# 16_RK3588_MIPI_Interface.net
KiCad netlist of a schematic drawn in Altium Designer
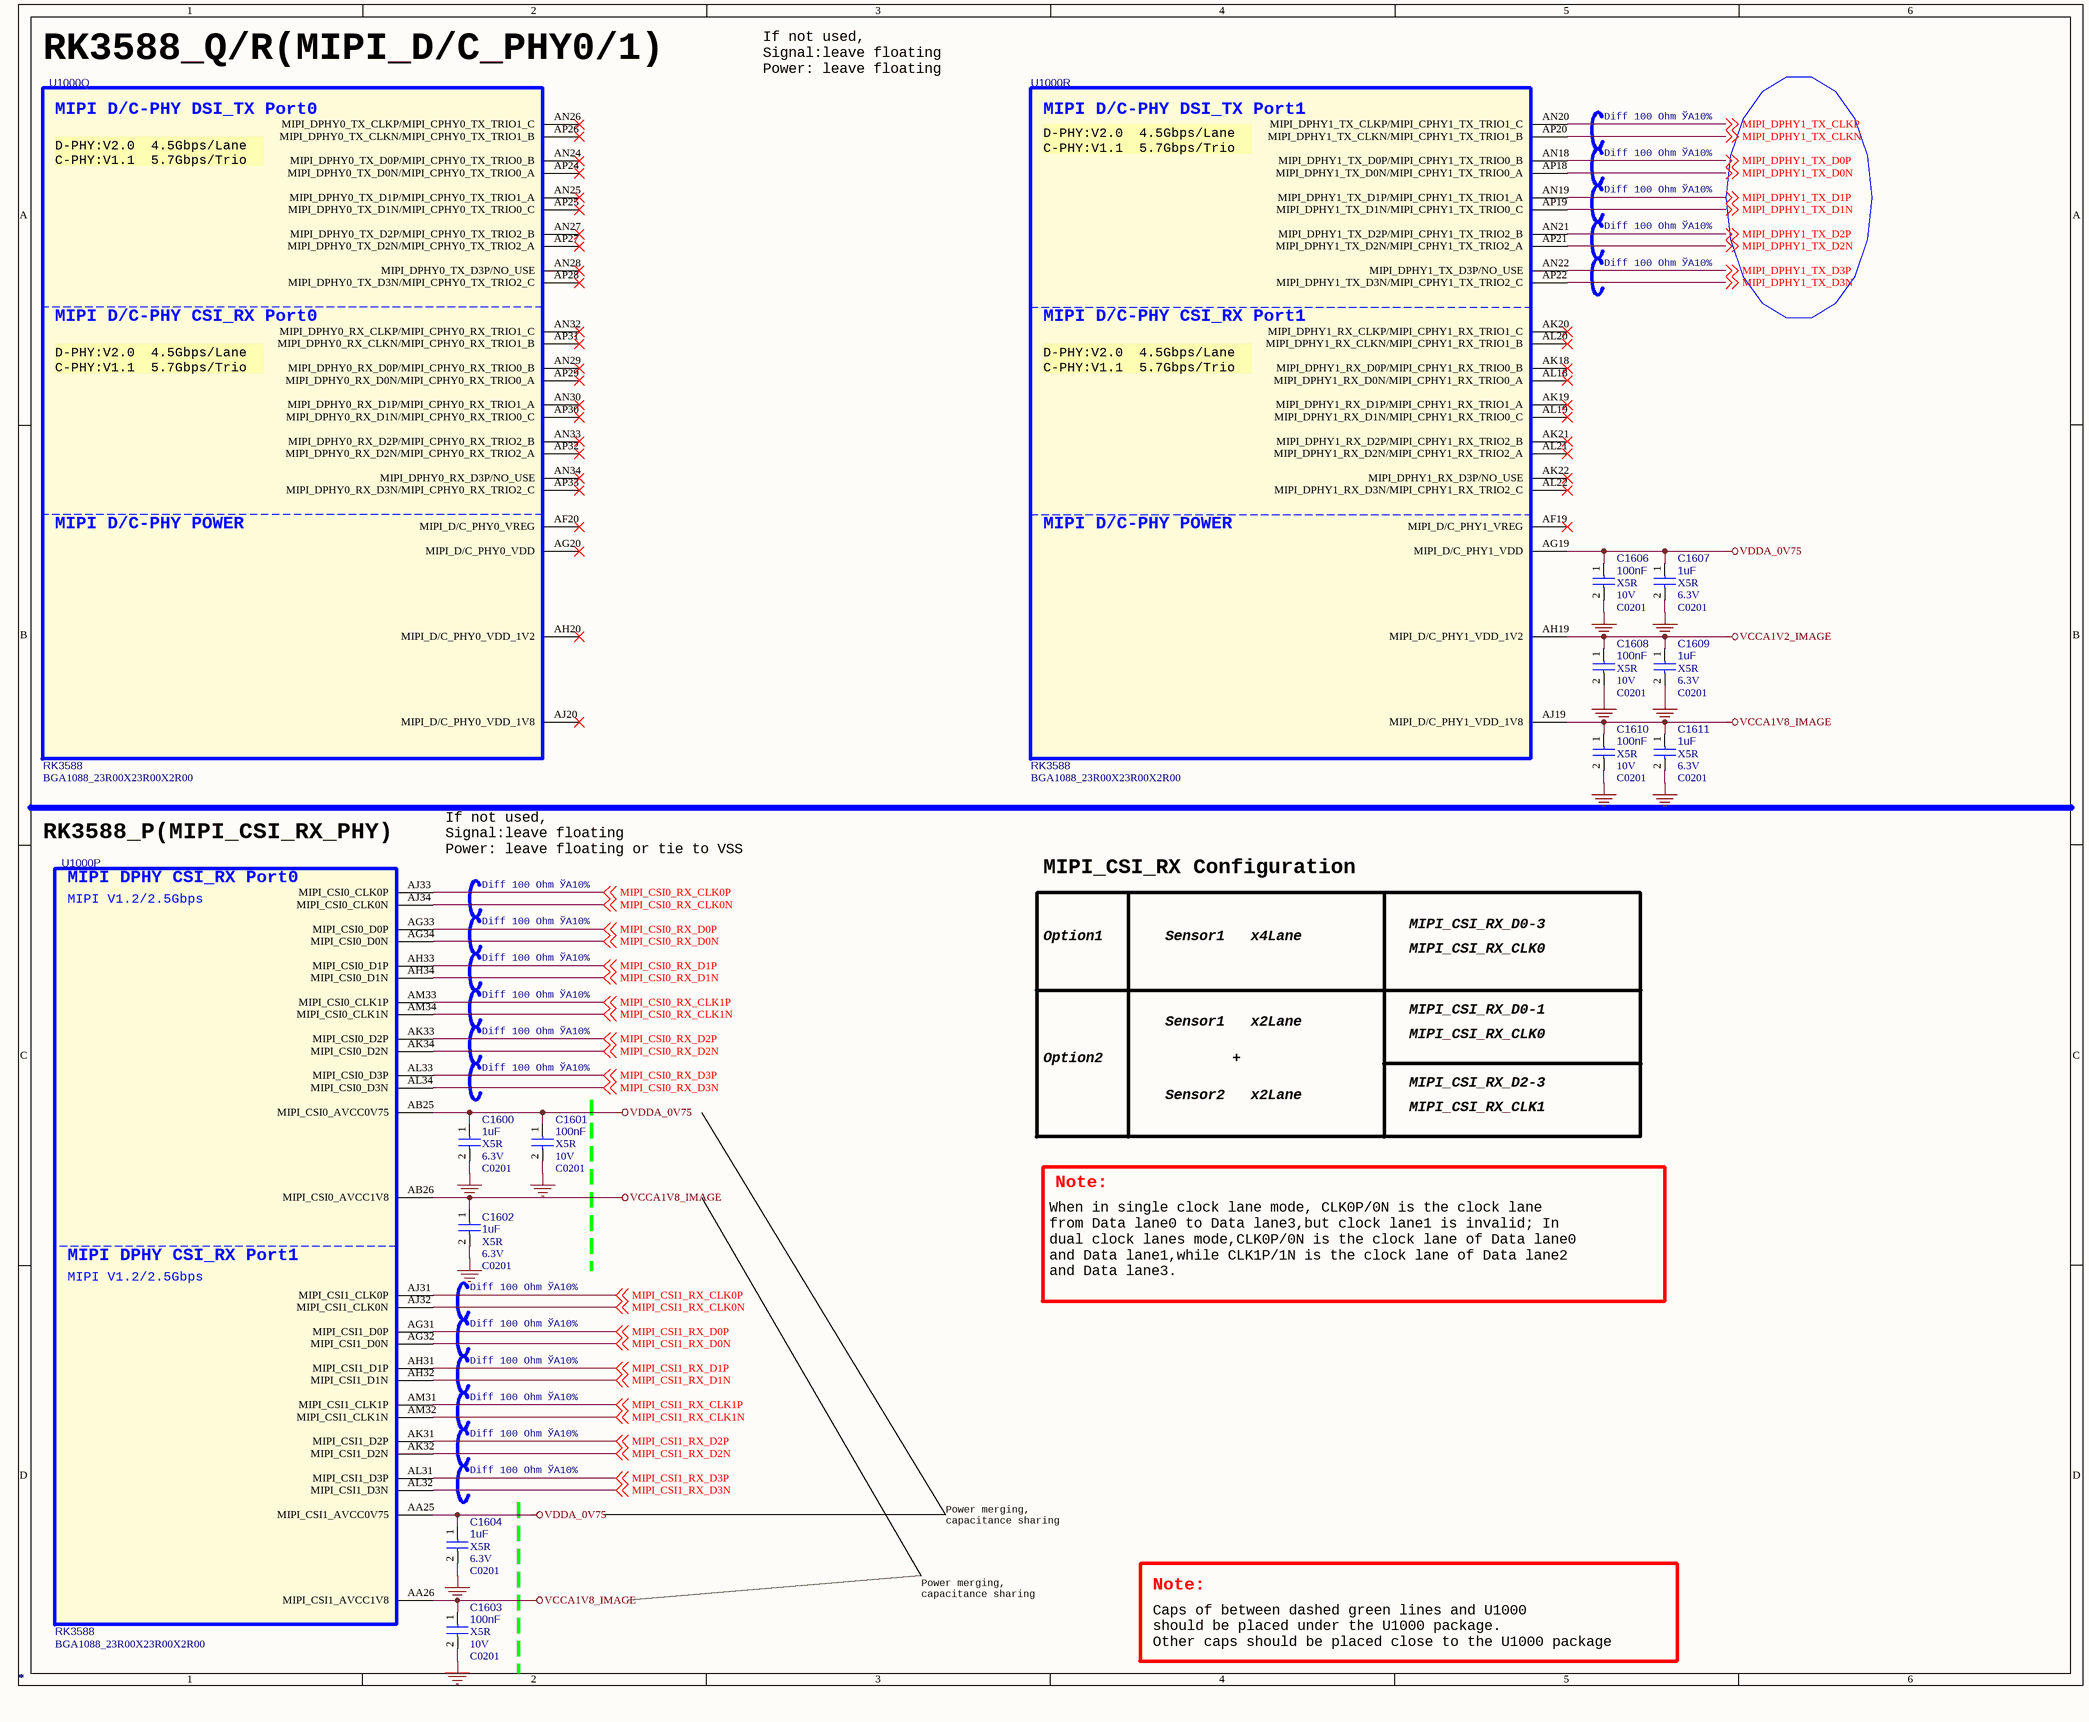
[diagram p0: 16.RK3588_MIPI  Interface.SchDoc]

(export (version "E")
  (design (tool "Eeschema 10.0.6"))
  (components
    (comp (ref "C1600")
      (value "*")
      (footprint "C0201")
      (description "cap,1.00uF,+/-20%,6.3V,X5R,C0201")
      (fields
        (field (name "VOLTAGE") "6.3V")
        (field (name "PCB FOOTPRINT") "C0201")
        (field (name "DIELECTRIC") "X5R")
        (field (name "TOLERANCE") "20%")
        (field (name "MANUFACTURER") "TDK")
        (field (name "ALTIUM_UNNAMED_1") "1uF")
        (field (name "CREATED BY") "JJJ")
      )
      (libsource (lib "*") (part "CAP NP"))
    )
    (comp (ref "C1601")
      (value "*")
      (footprint "C0201")
      (description "cap,100.00nF,+/-10%,10V,X5R,C0201")
      (fields
        (field (name "VOLTAGE") "10V")
        (field (name "PCB FOOTPRINT") "C0201")
        (field (name "DIELECTRIC") "X5R")
        (field (name "TOLERANCE") "10%")
        (field (name "MANUFACTURER") "TDK")
        (field (name "ALTIUM_UNNAMED_1") "100nF")
        (field (name "CREATED BY") "JJJ")
      )
      (libsource (lib "*") (part "CAP NP"))
    )
    (comp (ref "C1602")
      (value "*")
      (footprint "C0201")
      (description "cap,1.00uF,+/-20%,6.3V,X5R,C0201")
      (fields
        (field (name "VOLTAGE") "6.3V")
        (field (name "PCB FOOTPRINT") "C0201")
        (field (name "DIELECTRIC") "X5R")
        (field (name "TOLERANCE") "20%")
        (field (name "MANUFACTURER") "TDK")
        (field (name "ALTIUM_UNNAMED_1") "1uF")
        (field (name "CREATED BY") "JJJ")
      )
      (libsource (lib "*") (part "CAP NP"))
    )
    (comp (ref "C1603")
      (value "*")
      (footprint "C0201")
      (description "cap,100.00nF,+/-10%,10V,X5R,C0201")
      (fields
        (field (name "VOLTAGE") "10V")
        (field (name "PCB FOOTPRINT") "C0201")
        (field (name "DIELECTRIC") "X5R")
        (field (name "TOLERANCE") "10%")
        (field (name "MANUFACTURER") "TDK")
        (field (name "ALTIUM_UNNAMED_1") "100nF")
        (field (name "CREATED BY") "JJJ")
      )
      (libsource (lib "*") (part "CAP NP"))
    )
    (comp (ref "C1604")
      (value "*")
      (footprint "C0201")
      (description "cap,1.00uF,+/-20%,6.3V,X5R,C0201")
      (fields
        (field (name "VOLTAGE") "6.3V")
        (field (name "PCB FOOTPRINT") "C0201")
        (field (name "DIELECTRIC") "X5R")
        (field (name "MANUFACTURER") "TDK")
        (field (name "TOLERANCE") "20%")
        (field (name "ALTIUM_UNNAMED_1") "1uF")
        (field (name "CREATED BY") "JJJ")
      )
      (libsource (lib "*") (part "CAP NP"))
    )
    (comp (ref "C1606")
      (value "*")
      (footprint "C0201")
      (description "cap,100.00nF,+/-10%,10V,X5R,C0201")
      (fields
        (field (name "VOLTAGE") "10V")
        (field (name "PCB FOOTPRINT") "C0201")
        (field (name "DIELECTRIC") "X5R")
        (field (name "MANUFACTURER") "TDK")
        (field (name "TOLERANCE") "10%")
        (field (name "ALTIUM_UNNAMED_1") "100nF")
        (field (name "CREATED BY") "JJJ")
      )
      (libsource (lib "*") (part "CAP NP"))
    )
    (comp (ref "C1607")
      (value "*")
      (footprint "C0201")
      (description "cap,1.00uF,+/-20%,6.3V,X5R,C0201")
      (fields
        (field (name "VOLTAGE") "6.3V")
        (field (name "PCB FOOTPRINT") "C0201")
        (field (name "DIELECTRIC") "X5R")
        (field (name "TOLERANCE") "20%")
        (field (name "MANUFACTURER") "TDK")
        (field (name "ALTIUM_UNNAMED_1") "1uF")
        (field (name "CREATED BY") "JJJ")
      )
      (libsource (lib "*") (part "CAP NP"))
    )
    (comp (ref "C1608")
      (value "*")
      (footprint "C0201")
      (description "cap,100.00nF,+/-10%,10V,X5R,C0201")
      (fields
        (field (name "VOLTAGE") "10V")
        (field (name "PCB FOOTPRINT") "C0201")
        (field (name "DIELECTRIC") "X5R")
        (field (name "MANUFACTURER") "TDK")
        (field (name "TOLERANCE") "10%")
        (field (name "ALTIUM_UNNAMED_1") "100nF")
        (field (name "CREATED BY") "JJJ")
      )
      (libsource (lib "*") (part "CAP NP"))
    )
    (comp (ref "C1609")
      (value "*")
      (footprint "C0201")
      (description "cap,1.00uF,+/-20%,6.3V,X5R,C0201")
      (fields
        (field (name "VOLTAGE") "6.3V")
        (field (name "PCB FOOTPRINT") "C0201")
        (field (name "DIELECTRIC") "X5R")
        (field (name "TOLERANCE") "20%")
        (field (name "MANUFACTURER") "TDK")
        (field (name "ALTIUM_UNNAMED_1") "1uF")
        (field (name "CREATED BY") "JJJ")
      )
      (libsource (lib "*") (part "CAP NP"))
    )
    (comp (ref "C1610")
      (value "*")
      (footprint "C0201")
      (description "cap,100.00nF,+/-10%,10V,X5R,C0201")
      (fields
        (field (name "VOLTAGE") "10V")
        (field (name "PCB FOOTPRINT") "C0201")
        (field (name "DIELECTRIC") "X5R")
        (field (name "MANUFACTURER") "TDK")
        (field (name "TOLERANCE") "10%")
        (field (name "ALTIUM_UNNAMED_1") "100nF")
        (field (name "CREATED BY") "JJJ")
      )
      (libsource (lib "*") (part "CAP NP"))
    )
    (comp (ref "C1611")
      (value "*")
      (footprint "C0201")
      (description "cap,1.00uF,+/-20%,6.3V,X5R,C0201")
      (fields
        (field (name "VOLTAGE") "6.3V")
        (field (name "PCB FOOTPRINT") "C0201")
        (field (name "DIELECTRIC") "X5R")
        (field (name "TOLERANCE") "20%")
        (field (name "MANUFACTURER") "TDK")
        (field (name "ALTIUM_UNNAMED_1") "1uF")
        (field (name "CREATED BY") "JJJ")
      )
      (libsource (lib "*") (part "CAP NP"))
    )
    (comp (ref "U1000")
      (value "*")
      (footprint "BGA1088_23R00X23R00X2R00")
      (description "ROCKCHIP SOC")
      (fields
        (field (name "MANUFACTURER") "Rockchip (ИрРѕОў)")
        (field (name "PCB FOOTPRINT") "BGA1088_23R00X23R00X2R00")
        (field (name "ALTIUM_UNNAMED_1") "RK3588")
        (field (name "CREATED BY") "YWQ")
      )
      (libsource (lib "*") (part "SOC_RK3588"))
    )
  )
  (nets
    (net (code "1") (name "GND") (class "Default")
      (node (ref "C1600") (pin "2") (pinfunction "2_2") (pintype "passive"))
      (node (ref "C1601") (pin "2") (pinfunction "2_2") (pintype "passive"))
      (node (ref "C1602") (pin "2") (pinfunction "2_2") (pintype "passive"))
      (node (ref "C1603") (pin "2") (pinfunction "2_2") (pintype "passive"))
      (node (ref "C1604") (pin "2") (pinfunction "2_2") (pintype "passive"))
      (node (ref "C1606") (pin "2") (pinfunction "2_2") (pintype "passive"))
      (node (ref "C1607") (pin "2") (pinfunction "2_2") (pintype "passive"))
      (node (ref "C1608") (pin "2") (pinfunction "2_2") (pintype "passive"))
      (node (ref "C1609") (pin "2") (pinfunction "2_2") (pintype "passive"))
      (node (ref "C1610") (pin "2") (pinfunction "2_2") (pintype "passive"))
      (node (ref "C1611") (pin "2") (pinfunction "2_2") (pintype "passive"))
    )
    (net (code "2") (name "MIPI_CSI0_RX_CLK0N") (class "Default")
      (node (ref "U1000") (pin "AJ34") (pinfunction "MIPI_CSI0_CLK0N_AJ34") (pintype "passive"))
    )
    (net (code "3") (name "MIPI_CSI0_RX_CLK0P") (class "Default")
      (node (ref "U1000") (pin "AJ33") (pinfunction "MIPI_CSI0_CLK0P_AJ33") (pintype "passive"))
    )
    (net (code "4") (name "MIPI_CSI0_RX_CLK1N") (class "Default")
      (node (ref "U1000") (pin "AM34") (pinfunction "MIPI_CSI0_CLK1N_AM34") (pintype "passive"))
    )
    (net (code "5") (name "MIPI_CSI0_RX_CLK1P") (class "Default")
      (node (ref "U1000") (pin "AM33") (pinfunction "MIPI_CSI0_CLK1P_AM33") (pintype "passive"))
    )
    (net (code "6") (name "MIPI_CSI0_RX_D0N") (class "Default")
      (node (ref "U1000") (pin "AG34") (pinfunction "MIPI_CSI0_D0N_AG34") (pintype "passive"))
    )
    (net (code "7") (name "MIPI_CSI0_RX_D0P") (class "Default")
      (node (ref "U1000") (pin "AG33") (pinfunction "MIPI_CSI0_D0P_AG33") (pintype "passive"))
    )
    (net (code "8") (name "MIPI_CSI0_RX_D1N") (class "Default")
      (node (ref "U1000") (pin "AH34") (pinfunction "MIPI_CSI0_D1N_AH34") (pintype "passive"))
    )
    (net (code "9") (name "MIPI_CSI0_RX_D1P") (class "Default")
      (node (ref "U1000") (pin "AH33") (pinfunction "MIPI_CSI0_D1P_AH33") (pintype "passive"))
    )
    (net (code "10") (name "MIPI_CSI0_RX_D2N") (class "Default")
      (node (ref "U1000") (pin "AK34") (pinfunction "MIPI_CSI0_D2N_AK34") (pintype "passive"))
    )
    (net (code "11") (name "MIPI_CSI0_RX_D2P") (class "Default")
      (node (ref "U1000") (pin "AK33") (pinfunction "MIPI_CSI0_D2P_AK33") (pintype "passive"))
    )
    (net (code "12") (name "MIPI_CSI0_RX_D3N") (class "Default")
      (node (ref "U1000") (pin "AL34") (pinfunction "MIPI_CSI0_D3N_AL34") (pintype "passive"))
    )
    (net (code "13") (name "MIPI_CSI0_RX_D3P") (class "Default")
      (node (ref "U1000") (pin "AL33") (pinfunction "MIPI_CSI0_D3P_AL33") (pintype "passive"))
    )
    (net (code "14") (name "MIPI_CSI1_RX_CLK0N") (class "Default")
      (node (ref "U1000") (pin "AJ32") (pinfunction "MIPI_CSI1_CLK0N_AJ32") (pintype "passive"))
    )
    (net (code "15") (name "MIPI_CSI1_RX_CLK0P") (class "Default")
      (node (ref "U1000") (pin "AJ31") (pinfunction "MIPI_CSI1_CLK0P_AJ31") (pintype "passive"))
    )
    (net (code "16") (name "MIPI_CSI1_RX_CLK1N") (class "Default")
      (node (ref "U1000") (pin "AM32") (pinfunction "MIPI_CSI1_CLK1N_AM32") (pintype "passive"))
    )
    (net (code "17") (name "MIPI_CSI1_RX_CLK1P") (class "Default")
      (node (ref "U1000") (pin "AM31") (pinfunction "MIPI_CSI1_CLK1P_AM31") (pintype "passive"))
    )
    (net (code "18") (name "MIPI_CSI1_RX_D0N") (class "Default")
      (node (ref "U1000") (pin "AG32") (pinfunction "MIPI_CSI1_D0N_AG32") (pintype "passive"))
    )
    (net (code "19") (name "MIPI_CSI1_RX_D0P") (class "Default")
      (node (ref "U1000") (pin "AG31") (pinfunction "MIPI_CSI1_D0P_AG31") (pintype "passive"))
    )
    (net (code "20") (name "MIPI_CSI1_RX_D1N") (class "Default")
      (node (ref "U1000") (pin "AH32") (pinfunction "MIPI_CSI1_D1N_AH32") (pintype "passive"))
    )
    (net (code "21") (name "MIPI_CSI1_RX_D1P") (class "Default")
      (node (ref "U1000") (pin "AH31") (pinfunction "MIPI_CSI1_D1P_AH31") (pintype "passive"))
    )
    (net (code "22") (name "MIPI_CSI1_RX_D2N") (class "Default")
      (node (ref "U1000") (pin "AK32") (pinfunction "MIPI_CSI1_D2N_AK32") (pintype "passive"))
    )
    (net (code "23") (name "MIPI_CSI1_RX_D2P") (class "Default")
      (node (ref "U1000") (pin "AK31") (pinfunction "MIPI_CSI1_D2P_AK31") (pintype "passive"))
    )
    (net (code "24") (name "MIPI_CSI1_RX_D3N") (class "Default")
      (node (ref "U1000") (pin "AL32") (pinfunction "MIPI_CSI1_D3N_AL32") (pintype "passive"))
    )
    (net (code "25") (name "MIPI_CSI1_RX_D3P") (class "Default")
      (node (ref "U1000") (pin "AL31") (pinfunction "MIPI_CSI1_D3P_AL31") (pintype "passive"))
    )
    (net (code "26") (name "MIPI_DPHY1_TX_CLKN") (class "Default")
      (node (ref "U1000") (pin "AP20") (pinfunction "MIPI_DPHY1_TX_CLKN/MIPI_CPHY1_TX_TRIO1_B_AP20") (pintype "passive"))
    )
    (net (code "27") (name "MIPI_DPHY1_TX_CLKP") (class "Default")
      (node (ref "U1000") (pin "AN20") (pinfunction "MIPI_DPHY1_TX_CLKP/MIPI_CPHY1_TX_TRIO1_C_AN20") (pintype "passive"))
    )
    (net (code "28") (name "MIPI_DPHY1_TX_D0N") (class "Default")
      (node (ref "U1000") (pin "AP18") (pinfunction "MIPI_DPHY1_TX_D0N/MIPI_CPHY1_TX_TRIO0_A_AP18") (pintype "passive"))
    )
    (net (code "29") (name "MIPI_DPHY1_TX_D0P") (class "Default")
      (node (ref "U1000") (pin "AN18") (pinfunction "MIPI_DPHY1_TX_D0P/MIPI_CPHY1_TX_TRIO0_B_AN18") (pintype "passive"))
    )
    (net (code "30") (name "MIPI_DPHY1_TX_D1N") (class "Default")
      (node (ref "U1000") (pin "AP19") (pinfunction "MIPI_DPHY1_TX_D1N/MIPI_CPHY1_TX_TRIO0_C_AP19") (pintype "passive"))
    )
    (net (code "31") (name "MIPI_DPHY1_TX_D1P") (class "Default")
      (node (ref "U1000") (pin "AN19") (pinfunction "MIPI_DPHY1_TX_D1P/MIPI_CPHY1_TX_TRIO1_A_AN19") (pintype "passive"))
    )
    (net (code "32") (name "MIPI_DPHY1_TX_D2N") (class "Default")
      (node (ref "U1000") (pin "AP21") (pinfunction "MIPI_DPHY1_TX_D2N/MIPI_CPHY1_TX_TRIO2_A_AP21") (pintype "passive"))
    )
    (net (code "33") (name "MIPI_DPHY1_TX_D2P") (class "Default")
      (node (ref "U1000") (pin "AN21") (pinfunction "MIPI_DPHY1_TX_D2P/MIPI_CPHY1_TX_TRIO2_B_AN21") (pintype "passive"))
    )
    (net (code "34") (name "MIPI_DPHY1_TX_D3N") (class "Default")
      (node (ref "U1000") (pin "AP22") (pinfunction "MIPI_DPHY1_TX_D3N/MIPI_CPHY1_TX_TRIO2_C_AP22") (pintype "passive"))
    )
    (net (code "35") (name "MIPI_DPHY1_TX_D3P") (class "Default")
      (node (ref "U1000") (pin "AN22") (pinfunction "MIPI_DPHY1_TX_D3P/NO_USE_AN22") (pintype "passive"))
    )
    (net (code "36") (name "VCCA1V2_IMAGE") (class "Default")
      (node (ref "C1608") (pin "1") (pinfunction "1_1") (pintype "passive"))
      (node (ref "C1609") (pin "1") (pinfunction "1_1") (pintype "passive"))
      (node (ref "U1000") (pin "AH19") (pinfunction "MIPI_D/C_PHY1_VDD_1V2_AH19") (pintype "passive"))
    )
    (net (code "37") (name "VCCA1V8_IMAGE") (class "Default")
      (node (ref "C1602") (pin "1") (pinfunction "1_1") (pintype "passive"))
      (node (ref "C1603") (pin "1") (pinfunction "1_1") (pintype "passive"))
      (node (ref "C1610") (pin "1") (pinfunction "1_1") (pintype "passive"))
      (node (ref "C1611") (pin "1") (pinfunction "1_1") (pintype "passive"))
      (node (ref "U1000") (pin "AA26") (pinfunction "MIPI_CSI1_AVCC1V8_AA26") (pintype "passive"))
      (node (ref "U1000") (pin "AB26") (pinfunction "MIPI_CSI0_AVCC1V8_AB26") (pintype "passive"))
      (node (ref "U1000") (pin "AJ19") (pinfunction "MIPI_D/C_PHY1_VDD_1V8_AJ19") (pintype "passive"))
    )
    (net (code "38") (name "VDDA_0V75") (class "Default")
      (node (ref "C1600") (pin "1") (pinfunction "1_1") (pintype "passive"))
      (node (ref "C1601") (pin "1") (pinfunction "1_1") (pintype "passive"))
      (node (ref "C1604") (pin "1") (pinfunction "1_1") (pintype "passive"))
      (node (ref "C1606") (pin "1") (pinfunction "1_1") (pintype "passive"))
      (node (ref "C1607") (pin "1") (pinfunction "1_1") (pintype "passive"))
      (node (ref "U1000") (pin "AA25") (pinfunction "MIPI_CSI1_AVCC0V75_AA25") (pintype "passive"))
      (node (ref "U1000") (pin "AB25") (pinfunction "MIPI_CSI0_AVCC0V75_AB25") (pintype "passive"))
      (node (ref "U1000") (pin "AG19") (pinfunction "MIPI_D/C_PHY1_VDD_AG19") (pintype "passive"))
    )
    (net (code "39") (name "unconnected-(U1000Q-MIPI_DPHY0_RX_CLKN{slash}MIPI_CPHY0_RX_TRIO1_B-PadAP31)") (class "Default")
      (node (ref "U1000") (pin "AP31") (pinfunction "MIPI_DPHY0_RX_CLKN/MIPI_CPHY0_RX_TRIO1_B_AP31") (pintype "passive+no_connect"))
    )
    (net (code "40") (name "unconnected-(U1000Q-MIPI_DPHY0_RX_CLKP{slash}MIPI_CPHY0_RX_TRIO1_C-PadAN32)") (class "Default")
      (node (ref "U1000") (pin "AN32") (pinfunction "MIPI_DPHY0_RX_CLKP/MIPI_CPHY0_RX_TRIO1_C_AN32") (pintype "passive+no_connect"))
    )
    (net (code "41") (name "unconnected-(U1000Q-MIPI_DPHY0_RX_D0N{slash}MIPI_CPHY0_RX_TRIO0_A-PadAP29)") (class "Default")
      (node (ref "U1000") (pin "AP29") (pinfunction "MIPI_DPHY0_RX_D0N/MIPI_CPHY0_RX_TRIO0_A_AP29") (pintype "passive+no_connect"))
    )
    (net (code "42") (name "unconnected-(U1000Q-MIPI_DPHY0_RX_D0P{slash}MIPI_CPHY0_RX_TRIO0_B-PadAN29)") (class "Default")
      (node (ref "U1000") (pin "AN29") (pinfunction "MIPI_DPHY0_RX_D0P/MIPI_CPHY0_RX_TRIO0_B_AN29") (pintype "passive+no_connect"))
    )
    (net (code "43") (name "unconnected-(U1000Q-MIPI_DPHY0_RX_D1N{slash}MIPI_CPHY0_RX_TRIO0_C-PadAP30)") (class "Default")
      (node (ref "U1000") (pin "AP30") (pinfunction "MIPI_DPHY0_RX_D1N/MIPI_CPHY0_RX_TRIO0_C_AP30") (pintype "passive+no_connect"))
    )
    (net (code "44") (name "unconnected-(U1000Q-MIPI_DPHY0_RX_D1P{slash}MIPI_CPHY0_RX_TRIO1_A-PadAN30)") (class "Default")
      (node (ref "U1000") (pin "AN30") (pinfunction "MIPI_DPHY0_RX_D1P/MIPI_CPHY0_RX_TRIO1_A_AN30") (pintype "passive+no_connect"))
    )
    (net (code "45") (name "unconnected-(U1000Q-MIPI_DPHY0_RX_D2N{slash}MIPI_CPHY0_RX_TRIO2_A-PadAP32)") (class "Default")
      (node (ref "U1000") (pin "AP32") (pinfunction "MIPI_DPHY0_RX_D2N/MIPI_CPHY0_RX_TRIO2_A_AP32") (pintype "passive+no_connect"))
    )
    (net (code "46") (name "unconnected-(U1000Q-MIPI_DPHY0_RX_D2P{slash}MIPI_CPHY0_RX_TRIO2_B-PadAN33)") (class "Default")
      (node (ref "U1000") (pin "AN33") (pinfunction "MIPI_DPHY0_RX_D2P/MIPI_CPHY0_RX_TRIO2_B_AN33") (pintype "passive+no_connect"))
    )
    (net (code "47") (name "unconnected-(U1000Q-MIPI_DPHY0_RX_D3N{slash}MIPI_CPHY0_RX_TRIO2_C-PadAP33)") (class "Default")
      (node (ref "U1000") (pin "AP33") (pinfunction "MIPI_DPHY0_RX_D3N/MIPI_CPHY0_RX_TRIO2_C_AP33") (pintype "passive+no_connect"))
    )
    (net (code "48") (name "unconnected-(U1000Q-MIPI_DPHY0_RX_D3P{slash}NO_USE-PadAN34)") (class "Default")
      (node (ref "U1000") (pin "AN34") (pinfunction "MIPI_DPHY0_RX_D3P/NO_USE_AN34") (pintype "passive+no_connect"))
    )
    (net (code "49") (name "unconnected-(U1000Q-MIPI_DPHY0_TX_CLKN{slash}MIPI_CPHY0_TX_TRIO1_B-PadAP26)") (class "Default")
      (node (ref "U1000") (pin "AP26") (pinfunction "MIPI_DPHY0_TX_CLKN/MIPI_CPHY0_TX_TRIO1_B_AP26") (pintype "passive+no_connect"))
    )
    (net (code "50") (name "unconnected-(U1000Q-MIPI_DPHY0_TX_CLKP{slash}MIPI_CPHY0_TX_TRIO1_C-PadAN26)") (class "Default")
      (node (ref "U1000") (pin "AN26") (pinfunction "MIPI_DPHY0_TX_CLKP/MIPI_CPHY0_TX_TRIO1_C_AN26") (pintype "passive+no_connect"))
    )
    (net (code "51") (name "unconnected-(U1000Q-MIPI_DPHY0_TX_D0N{slash}MIPI_CPHY0_TX_TRIO0_A-PadAP24)") (class "Default")
      (node (ref "U1000") (pin "AP24") (pinfunction "MIPI_DPHY0_TX_D0N/MIPI_CPHY0_TX_TRIO0_A_AP24") (pintype "passive+no_connect"))
    )
    (net (code "52") (name "unconnected-(U1000Q-MIPI_DPHY0_TX_D0P{slash}MIPI_CPHY0_TX_TRIO0_B-PadAN24)") (class "Default")
      (node (ref "U1000") (pin "AN24") (pinfunction "MIPI_DPHY0_TX_D0P/MIPI_CPHY0_TX_TRIO0_B_AN24") (pintype "passive+no_connect"))
    )
    (net (code "53") (name "unconnected-(U1000Q-MIPI_DPHY0_TX_D1N{slash}MIPI_CPHY0_TX_TRIO0_C-PadAP25)") (class "Default")
      (node (ref "U1000") (pin "AP25") (pinfunction "MIPI_DPHY0_TX_D1N/MIPI_CPHY0_TX_TRIO0_C_AP25") (pintype "passive+no_connect"))
    )
    (net (code "54") (name "unconnected-(U1000Q-MIPI_DPHY0_TX_D1P{slash}MIPI_CPHY0_TX_TRIO1_A-PadAN25)") (class "Default")
      (node (ref "U1000") (pin "AN25") (pinfunction "MIPI_DPHY0_TX_D1P/MIPI_CPHY0_TX_TRIO1_A_AN25") (pintype "passive+no_connect"))
    )
    (net (code "55") (name "unconnected-(U1000Q-MIPI_DPHY0_TX_D2N{slash}MIPI_CPHY0_TX_TRIO2_A-PadAP27)") (class "Default")
      (node (ref "U1000") (pin "AP27") (pinfunction "MIPI_DPHY0_TX_D2N/MIPI_CPHY0_TX_TRIO2_A_AP27") (pintype "passive+no_connect"))
    )
    (net (code "56") (name "unconnected-(U1000Q-MIPI_DPHY0_TX_D2P{slash}MIPI_CPHY0_TX_TRIO2_B-PadAN27)") (class "Default")
      (node (ref "U1000") (pin "AN27") (pinfunction "MIPI_DPHY0_TX_D2P/MIPI_CPHY0_TX_TRIO2_B_AN27") (pintype "passive+no_connect"))
    )
    (net (code "57") (name "unconnected-(U1000Q-MIPI_DPHY0_TX_D3N{slash}MIPI_CPHY0_TX_TRIO2_C-PadAP28)") (class "Default")
      (node (ref "U1000") (pin "AP28") (pinfunction "MIPI_DPHY0_TX_D3N/MIPI_CPHY0_TX_TRIO2_C_AP28") (pintype "passive+no_connect"))
    )
    (net (code "58") (name "unconnected-(U1000Q-MIPI_DPHY0_TX_D3P{slash}NO_USE-PadAN28)") (class "Default")
      (node (ref "U1000") (pin "AN28") (pinfunction "MIPI_DPHY0_TX_D3P/NO_USE_AN28") (pintype "passive+no_connect"))
    )
    (net (code "59") (name "unconnected-(U1000Q-MIPI_D{slash}C_PHY0_VDD-PadAG20)") (class "Default")
      (node (ref "U1000") (pin "AG20") (pinfunction "MIPI_D/C_PHY0_VDD_AG20") (pintype "passive+no_connect"))
    )
    (net (code "60") (name "unconnected-(U1000Q-MIPI_D{slash}C_PHY0_VDD_1V2-PadAH20)") (class "Default")
      (node (ref "U1000") (pin "AH20") (pinfunction "MIPI_D/C_PHY0_VDD_1V2_AH20") (pintype "passive+no_connect"))
    )
    (net (code "61") (name "unconnected-(U1000Q-MIPI_D{slash}C_PHY0_VDD_1V8-PadAJ20)") (class "Default")
      (node (ref "U1000") (pin "AJ20") (pinfunction "MIPI_D/C_PHY0_VDD_1V8_AJ20") (pintype "passive+no_connect"))
    )
    (net (code "62") (name "unconnected-(U1000Q-MIPI_D{slash}C_PHY0_VREG-PadAF20)") (class "Default")
      (node (ref "U1000") (pin "AF20") (pinfunction "MIPI_D/C_PHY0_VREG_AF20") (pintype "passive+no_connect"))
    )
    (net (code "63") (name "unconnected-(U1000R-MIPI_DPHY1_RX_CLKN{slash}MIPI_CPHY1_RX_TRIO1_B-PadAL20)") (class "Default")
      (node (ref "U1000") (pin "AL20") (pinfunction "MIPI_DPHY1_RX_CLKN/MIPI_CPHY1_RX_TRIO1_B_AL20") (pintype "passive+no_connect"))
    )
    (net (code "64") (name "unconnected-(U1000R-MIPI_DPHY1_RX_CLKP{slash}MIPI_CPHY1_RX_TRIO1_C-PadAK20)") (class "Default")
      (node (ref "U1000") (pin "AK20") (pinfunction "MIPI_DPHY1_RX_CLKP/MIPI_CPHY1_RX_TRIO1_C_AK20") (pintype "passive+no_connect"))
    )
    (net (code "65") (name "unconnected-(U1000R-MIPI_DPHY1_RX_D0N{slash}MIPI_CPHY1_RX_TRIO0_A-PadAL18)") (class "Default")
      (node (ref "U1000") (pin "AL18") (pinfunction "MIPI_DPHY1_RX_D0N/MIPI_CPHY1_RX_TRIO0_A_AL18") (pintype "passive+no_connect"))
    )
    (net (code "66") (name "unconnected-(U1000R-MIPI_DPHY1_RX_D0P{slash}MIPI_CPHY1_RX_TRIO0_B-PadAK18)") (class "Default")
      (node (ref "U1000") (pin "AK18") (pinfunction "MIPI_DPHY1_RX_D0P/MIPI_CPHY1_RX_TRIO0_B_AK18") (pintype "passive+no_connect"))
    )
    (net (code "67") (name "unconnected-(U1000R-MIPI_DPHY1_RX_D1N{slash}MIPI_CPHY1_RX_TRIO0_C-PadAL19)") (class "Default")
      (node (ref "U1000") (pin "AL19") (pinfunction "MIPI_DPHY1_RX_D1N/MIPI_CPHY1_RX_TRIO0_C_AL19") (pintype "passive+no_connect"))
    )
    (net (code "68") (name "unconnected-(U1000R-MIPI_DPHY1_RX_D1P{slash}MIPI_CPHY1_RX_TRIO1_A-PadAK19)") (class "Default")
      (node (ref "U1000") (pin "AK19") (pinfunction "MIPI_DPHY1_RX_D1P/MIPI_CPHY1_RX_TRIO1_A_AK19") (pintype "passive+no_connect"))
    )
    (net (code "69") (name "unconnected-(U1000R-MIPI_DPHY1_RX_D2N{slash}MIPI_CPHY1_RX_TRIO2_A-PadAL21)") (class "Default")
      (node (ref "U1000") (pin "AL21") (pinfunction "MIPI_DPHY1_RX_D2N/MIPI_CPHY1_RX_TRIO2_A_AL21") (pintype "passive+no_connect"))
    )
    (net (code "70") (name "unconnected-(U1000R-MIPI_DPHY1_RX_D2P{slash}MIPI_CPHY1_RX_TRIO2_B-PadAK21)") (class "Default")
      (node (ref "U1000") (pin "AK21") (pinfunction "MIPI_DPHY1_RX_D2P/MIPI_CPHY1_RX_TRIO2_B_AK21") (pintype "passive+no_connect"))
    )
    (net (code "71") (name "unconnected-(U1000R-MIPI_DPHY1_RX_D3N{slash}MIPI_CPHY1_RX_TRIO2_C-PadAL22)") (class "Default")
      (node (ref "U1000") (pin "AL22") (pinfunction "MIPI_DPHY1_RX_D3N/MIPI_CPHY1_RX_TRIO2_C_AL22") (pintype "passive+no_connect"))
    )
    (net (code "72") (name "unconnected-(U1000R-MIPI_DPHY1_RX_D3P{slash}NO_USE-PadAK22)") (class "Default")
      (node (ref "U1000") (pin "AK22") (pinfunction "MIPI_DPHY1_RX_D3P/NO_USE_AK22") (pintype "passive+no_connect"))
    )
    (net (code "73") (name "unconnected-(U1000R-MIPI_D{slash}C_PHY1_VREG-PadAF19)") (class "Default")
      (node (ref "U1000") (pin "AF19") (pinfunction "MIPI_D/C_PHY1_VREG_AF19") (pintype "passive+no_connect"))
    )
  )
)
